# cube_bottom_4.net
KiCad netlist of a schematic drawn in EAGLE
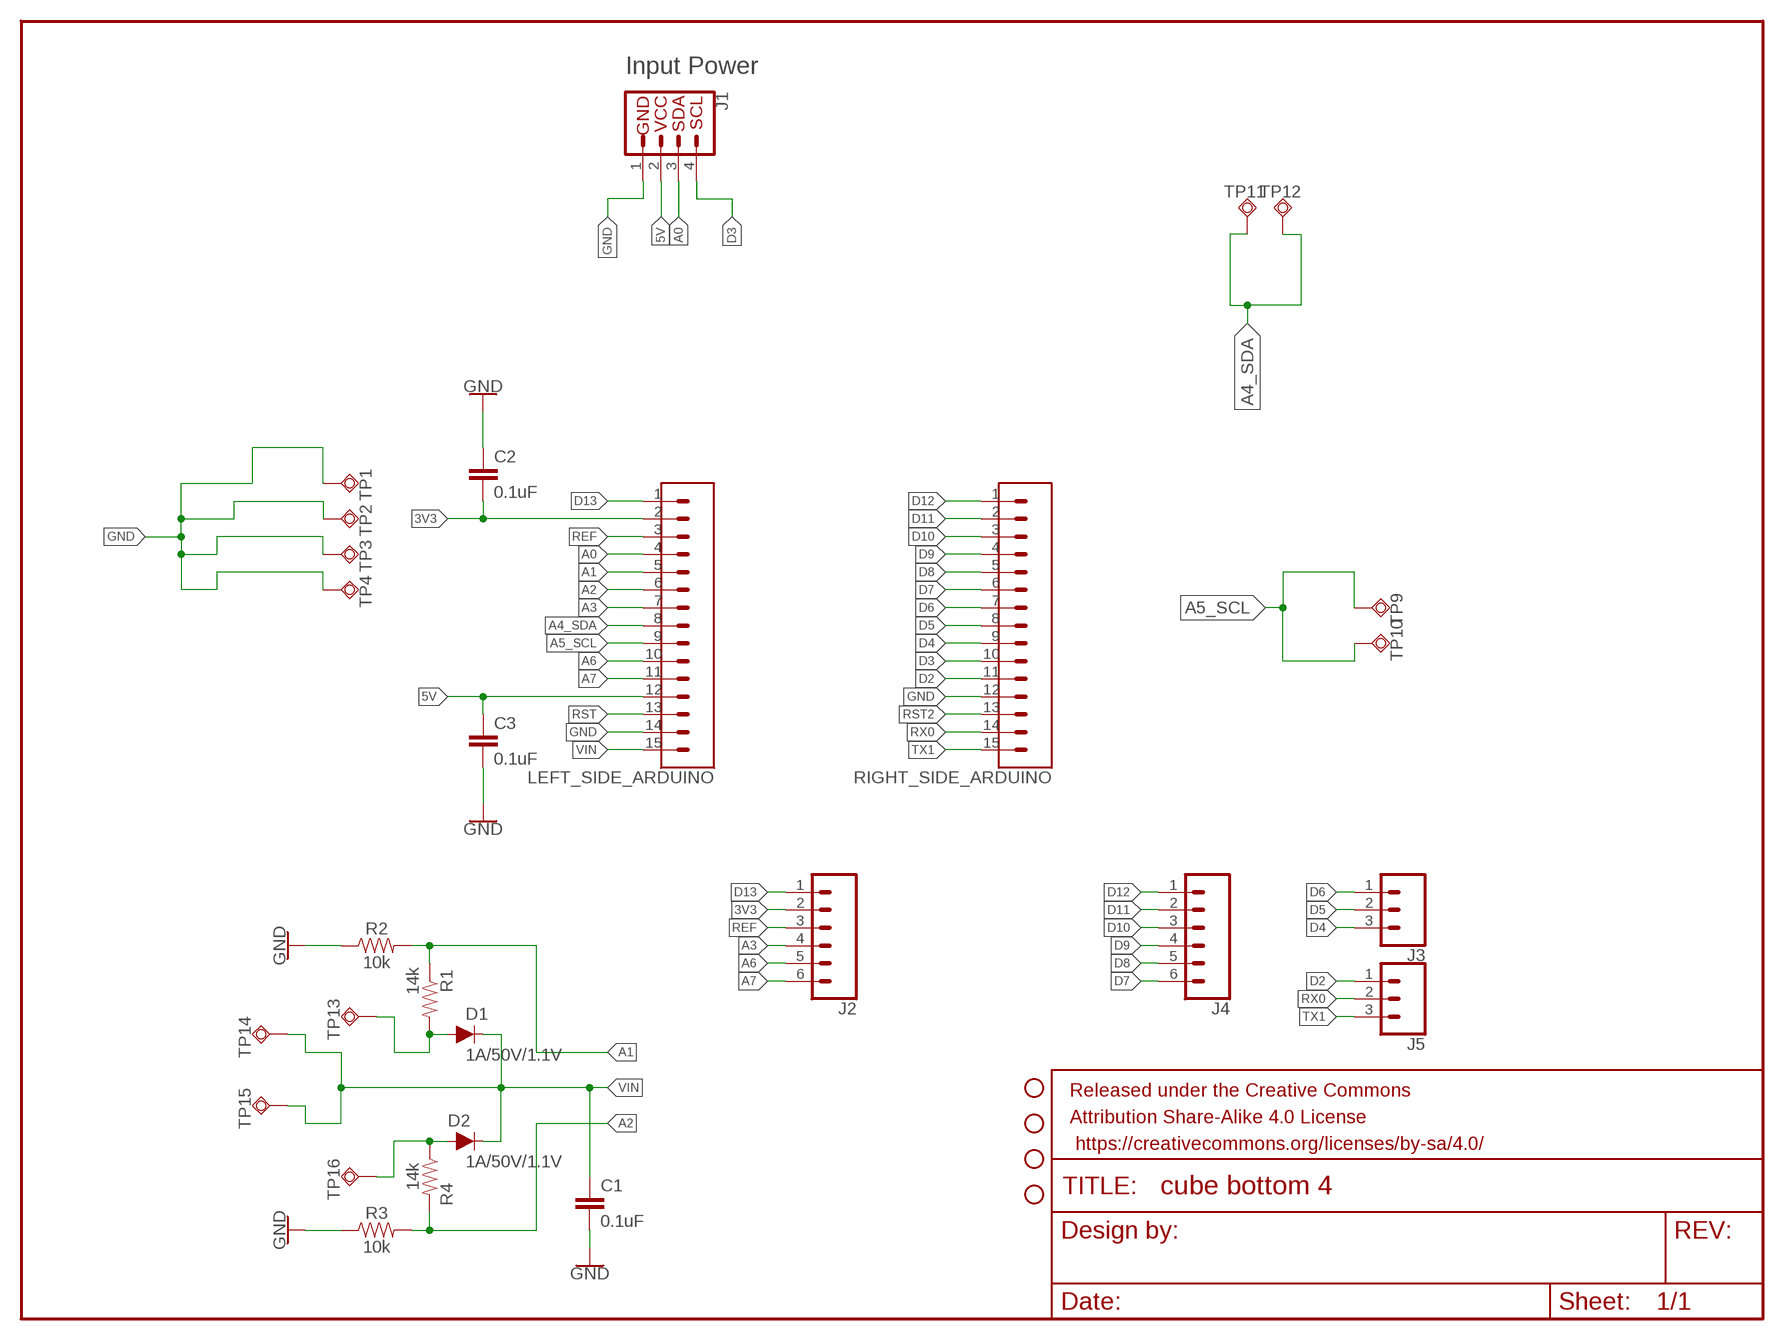
[diagram p0: schematic, sheet 1]

(export (version "E")
  (design (tool "Eeschema 10.0.6"))
  (components
    (comp (ref "C1")
      (value "0.1uF")
      (footprint "eagle-import:0603")
      (libsource (lib "eagle-import") (part "0.1UF-0603-25V-5%"))
    )
    (comp (ref "C2")
      (value "0.1uF")
      (footprint "eagle-import:0603")
      (libsource (lib "eagle-import") (part "0.1UF-0603-25V-(+80/-20%)"))
    )
    (comp (ref "C3")
      (value "0.1uF")
      (footprint "eagle-import:0603")
      (libsource (lib "eagle-import") (part "0.1UF-0603-25V-(+80/-20%)"))
    )
    (comp (ref "D1")
      (value "1A/50V/1.1V")
      (footprint "eagle-import:DIODE-1N4001")
      (libsource (lib "eagle-import") (part "DIODE-PTH"))
    )
    (comp (ref "D2")
      (value "1A/50V/1.1V")
      (footprint "eagle-import:DIODE-1N4001")
      (libsource (lib "eagle-import") (part "DIODE-PTH"))
    )
    (comp (ref "FRAME1")
      (value "FRAME-LETTERNO_PACKAGE")
      (footprint "eagle-import:DUMMY")
      (fields (field (name "DESIGNER") "Nobody"))
      (libsource (lib "eagle-import") (part "FRAME-LETTERNO_PACKAGE"))
    )
    (comp (ref "H1")
      (value "STAND-OFF")
      (footprint "eagle-import:STAND-OFF")
      (libsource (lib "eagle-import") (part "STAND-OFF"))
    )
    (comp (ref "H2")
      (value "STAND-OFF")
      (footprint "eagle-import:STAND-OFF")
      (libsource (lib "eagle-import") (part "STAND-OFF"))
    )
    (comp (ref "H3")
      (value "STAND-OFF")
      (footprint "eagle-import:STAND-OFF")
      (libsource (lib "eagle-import") (part "STAND-OFF"))
    )
    (comp (ref "H4")
      (value "STAND-OFF")
      (footprint "eagle-import:STAND-OFF")
      (libsource (lib "eagle-import") (part "STAND-OFF"))
    )
    (comp (ref "J1")
      (value "QWIIC_CONNECTORJS-1MM")
      (footprint "eagle-import:1X04_1MM_RA")
      (libsource (lib "eagle-import") (part "QWIIC_CONNECTORJS-1MM"))
    )
    (comp (ref "J2")
      (value "CONN_06SILK_FEMALE_PTH")
      (footprint "eagle-import:1X06")
      (libsource (lib "eagle-import") (part "CONN_06SILK_FEMALE_PTH"))
    )
    (comp (ref "J3")
      (value "CONN_03")
      (footprint "eagle-import:1X03")
      (libsource (lib "eagle-import") (part "CONN_03"))
    )
    (comp (ref "J4")
      (value "CONN_06SILK_FEMALE_PTH")
      (footprint "eagle-import:1X06")
      (libsource (lib "eagle-import") (part "CONN_06SILK_FEMALE_PTH"))
    )
    (comp (ref "J5")
      (value "CONN_03")
      (footprint "eagle-import:1X03")
      (libsource (lib "eagle-import") (part "CONN_03"))
    )
    (comp (ref "LEFT_SIDE_ARDUINO")
      (value "CONN_06SMD_MALE")
      (footprint "eagle-import:1X15_SMD_MALE")
      (libsource (lib "eagle-import") (part "capstone footprints_CONN_06SMD_MALE"))
    )
    (comp (ref "R1")
      (value "14k")
      (footprint "eagle-import:0603")
      (libsource (lib "eagle-import") (part "10KOHM-0603-1/10W-1%"))
    )
    (comp (ref "R2")
      (value "10k")
      (footprint "eagle-import:0603")
      (libsource (lib "eagle-import") (part "10KOHM-0603-1/10W-1%"))
    )
    (comp (ref "R3")
      (value "10k")
      (footprint "eagle-import:0603")
      (libsource (lib "eagle-import") (part "10KOHM-0603-1/10W-1%"))
    )
    (comp (ref "R4")
      (value "14k")
      (footprint "eagle-import:0603")
      (libsource (lib "eagle-import") (part "10KOHM-0603-1/10W-1%"))
    )
    (comp (ref "RIGHT_SIDE_ARDUINO")
      (value "CONN_06SMD_MALE")
      (footprint "eagle-import:1X15_SMD_MALE")
      (libsource (lib "eagle-import") (part "capstone footprints_CONN_06SMD_MALE"))
    )
    (comp (ref "TP1")
      (value "TPSQTP20SQ")
      (footprint "eagle-import:TP20SQ")
      (libsource (lib "eagle-import") (part "TPSQTP20SQ"))
    )
    (comp (ref "TP2")
      (value "TPSQTP20SQ")
      (footprint "eagle-import:TP20SQ")
      (libsource (lib "eagle-import") (part "TPSQTP20SQ"))
    )
    (comp (ref "TP3")
      (value "TPSQTP20SQ")
      (footprint "eagle-import:TP20SQ")
      (libsource (lib "eagle-import") (part "TPSQTP20SQ"))
    )
    (comp (ref "TP4")
      (value "TPSQTP20SQ")
      (footprint "eagle-import:TP20SQ")
      (libsource (lib "eagle-import") (part "TPSQTP20SQ"))
    )
    (comp (ref "TP9")
      (value "TPSQTP20SQ")
      (footprint "eagle-import:TP20SQ")
      (libsource (lib "eagle-import") (part "TPSQTP20SQ"))
    )
    (comp (ref "TP10")
      (value "TPSQTP20SQ")
      (footprint "eagle-import:TP20SQ")
      (libsource (lib "eagle-import") (part "TPSQTP20SQ"))
    )
    (comp (ref "TP11")
      (value "TPSQTP20SQ")
      (footprint "eagle-import:TP20SQ")
      (libsource (lib "eagle-import") (part "TPSQTP20SQ"))
    )
    (comp (ref "TP12")
      (value "TPSQTP20SQ")
      (footprint "eagle-import:TP20SQ")
      (libsource (lib "eagle-import") (part "TPSQTP20SQ"))
    )
    (comp (ref "TP13")
      (value "TPSQTP20SQ")
      (footprint "eagle-import:TP20SQ")
      (libsource (lib "eagle-import") (part "TPSQTP20SQ"))
    )
    (comp (ref "TP14")
      (value "TPSQTP20SQ")
      (footprint "eagle-import:TP20SQ")
      (libsource (lib "eagle-import") (part "TPSQTP20SQ"))
    )
    (comp (ref "TP15")
      (value "TPSQTP20SQ")
      (footprint "eagle-import:TP20SQ")
      (libsource (lib "eagle-import") (part "TPSQTP20SQ"))
    )
    (comp (ref "TP16")
      (value "TPSQTP20SQ")
      (footprint "eagle-import:TP20SQ")
      (libsource (lib "eagle-import") (part "TPSQTP20SQ"))
    )
  )
  (nets
    (net (code "1") (name "3V3") (class "Default")
      (node (ref "C2") (pin "2") (pinfunction "2_2") (pintype "passive"))
      (node (ref "J2") (pin "2") (pinfunction "2_2") (pintype "passive"))
      (node (ref "LEFT_SIDE_ARDUINO") (pin "2") (pinfunction "2_2") (pintype "passive"))
    )
    (net (code "2") (name "5V") (class "Default")
      (node (ref "C3") (pin "1") (pinfunction "1_1") (pintype "passive"))
      (node (ref "J1") (pin "2") (pinfunction "VCC_2") (pintype "power_in"))
      (node (ref "LEFT_SIDE_ARDUINO") (pin "12") (pinfunction "12_12") (pintype "passive"))
    )
    (net (code "3") (name "A0") (class "Default")
      (node (ref "J1") (pin "3") (pinfunction "SDA_3") (pintype "passive"))
      (node (ref "LEFT_SIDE_ARDUINO") (pin "4") (pinfunction "4_4") (pintype "passive"))
    )
    (net (code "4") (name "A1") (class "Default")
      (node (ref "LEFT_SIDE_ARDUINO") (pin "5") (pinfunction "5_5") (pintype "passive"))
      (node (ref "R1") (pin "1") (pinfunction "1_1") (pintype "passive"))
      (node (ref "R2") (pin "2") (pinfunction "2_2") (pintype "passive"))
    )
    (net (code "5") (name "A2") (class "Default")
      (node (ref "LEFT_SIDE_ARDUINO") (pin "6") (pinfunction "6_6") (pintype "passive"))
      (node (ref "R3") (pin "2") (pinfunction "2_2") (pintype "passive"))
      (node (ref "R4") (pin "2") (pinfunction "2_2") (pintype "passive"))
    )
    (net (code "6") (name "A3") (class "Default")
      (node (ref "J2") (pin "4") (pinfunction "4_4") (pintype "passive"))
      (node (ref "LEFT_SIDE_ARDUINO") (pin "7") (pinfunction "7_7") (pintype "passive"))
    )
    (net (code "7") (name "A4_SDA") (class "Default")
      (node (ref "LEFT_SIDE_ARDUINO") (pin "8") (pinfunction "8_8") (pintype "passive"))
      (node (ref "TP11") (pin "TP") (pinfunction "TP_TP") (pintype "input"))
      (node (ref "TP12") (pin "TP") (pinfunction "TP_TP") (pintype "input"))
    )
    (net (code "8") (name "A5_SCL") (class "Default")
      (node (ref "LEFT_SIDE_ARDUINO") (pin "9") (pinfunction "9_9") (pintype "passive"))
      (node (ref "TP10") (pin "TP") (pinfunction "TP_TP") (pintype "input"))
      (node (ref "TP9") (pin "TP") (pinfunction "TP_TP") (pintype "input"))
    )
    (net (code "9") (name "A6") (class "Default")
      (node (ref "J2") (pin "5") (pinfunction "5_5") (pintype "passive"))
      (node (ref "LEFT_SIDE_ARDUINO") (pin "10") (pinfunction "10_10") (pintype "passive"))
    )
    (net (code "10") (name "A7") (class "Default")
      (node (ref "J2") (pin "6") (pinfunction "6_6") (pintype "passive"))
      (node (ref "LEFT_SIDE_ARDUINO") (pin "11") (pinfunction "11_11") (pintype "passive"))
    )
    (net (code "11") (name "D2") (class "Default")
      (node (ref "J5") (pin "1") (pinfunction "1_1") (pintype "passive"))
      (node (ref "RIGHT_SIDE_ARDUINO") (pin "11") (pinfunction "11_11") (pintype "passive"))
    )
    (net (code "12") (name "D3") (class "Default")
      (node (ref "J1") (pin "4") (pinfunction "SCL_4") (pintype "passive"))
      (node (ref "RIGHT_SIDE_ARDUINO") (pin "10") (pinfunction "10_10") (pintype "passive"))
    )
    (net (code "13") (name "D4") (class "Default")
      (node (ref "J3") (pin "3") (pinfunction "3_3") (pintype "passive"))
      (node (ref "RIGHT_SIDE_ARDUINO") (pin "9") (pinfunction "9_9") (pintype "passive"))
    )
    (net (code "14") (name "D5") (class "Default")
      (node (ref "J3") (pin "2") (pinfunction "2_2") (pintype "passive"))
      (node (ref "RIGHT_SIDE_ARDUINO") (pin "8") (pinfunction "8_8") (pintype "passive"))
    )
    (net (code "15") (name "D6") (class "Default")
      (node (ref "J3") (pin "1") (pinfunction "1_1") (pintype "passive"))
      (node (ref "RIGHT_SIDE_ARDUINO") (pin "7") (pinfunction "7_7") (pintype "passive"))
    )
    (net (code "16") (name "D7") (class "Default")
      (node (ref "J4") (pin "6") (pinfunction "6_6") (pintype "passive"))
      (node (ref "RIGHT_SIDE_ARDUINO") (pin "6") (pinfunction "6_6") (pintype "passive"))
    )
    (net (code "17") (name "D8") (class "Default")
      (node (ref "J4") (pin "5") (pinfunction "5_5") (pintype "passive"))
      (node (ref "RIGHT_SIDE_ARDUINO") (pin "5") (pinfunction "5_5") (pintype "passive"))
    )
    (net (code "18") (name "D9") (class "Default")
      (node (ref "J4") (pin "4") (pinfunction "4_4") (pintype "passive"))
      (node (ref "RIGHT_SIDE_ARDUINO") (pin "4") (pinfunction "4_4") (pintype "passive"))
    )
    (net (code "19") (name "D10") (class "Default")
      (node (ref "J4") (pin "3") (pinfunction "3_3") (pintype "passive"))
      (node (ref "RIGHT_SIDE_ARDUINO") (pin "3") (pinfunction "3_3") (pintype "passive"))
    )
    (net (code "20") (name "D11") (class "Default")
      (node (ref "J4") (pin "2") (pinfunction "2_2") (pintype "passive"))
      (node (ref "RIGHT_SIDE_ARDUINO") (pin "2") (pinfunction "2_2") (pintype "passive"))
    )
    (net (code "21") (name "D12") (class "Default")
      (node (ref "J4") (pin "1") (pinfunction "1_1") (pintype "passive"))
      (node (ref "RIGHT_SIDE_ARDUINO") (pin "1") (pinfunction "1_1") (pintype "passive"))
    )
    (net (code "22") (name "D13") (class "Default")
      (node (ref "J2") (pin "1") (pinfunction "1_1") (pintype "passive"))
      (node (ref "LEFT_SIDE_ARDUINO") (pin "1") (pinfunction "1_1") (pintype "passive"))
    )
    (net (code "23") (name "GND") (class "Default")
      (node (ref "C1") (pin "2") (pinfunction "2_2") (pintype "passive"))
      (node (ref "C2") (pin "1") (pinfunction "1_1") (pintype "passive"))
      (node (ref "C3") (pin "2") (pinfunction "2_2") (pintype "passive"))
      (node (ref "J1") (pin "1") (pinfunction "GND_1") (pintype "power_in"))
      (node (ref "LEFT_SIDE_ARDUINO") (pin "14") (pinfunction "14_14") (pintype "passive"))
      (node (ref "R2") (pin "1") (pinfunction "1_1") (pintype "passive"))
      (node (ref "R3") (pin "1") (pinfunction "1_1") (pintype "passive"))
      (node (ref "RIGHT_SIDE_ARDUINO") (pin "12") (pinfunction "12_12") (pintype "passive"))
      (node (ref "TP1") (pin "TP") (pinfunction "TP_TP") (pintype "input"))
      (node (ref "TP2") (pin "TP") (pinfunction "TP_TP") (pintype "input"))
      (node (ref "TP3") (pin "TP") (pinfunction "TP_TP") (pintype "input"))
      (node (ref "TP4") (pin "TP") (pinfunction "TP_TP") (pintype "input"))
    )
    (net (code "24") (name "Net-(D1-PadA)") (class "Default")
      (node (ref "D1") (pin "A") (pinfunction "A_A") (pintype "passive"))
      (node (ref "R1") (pin "2") (pinfunction "2_2") (pintype "passive"))
      (node (ref "TP13") (pin "TP") (pinfunction "TP_TP") (pintype "input"))
    )
    (net (code "25") (name "Net-(D2-PadA)") (class "Default")
      (node (ref "D2") (pin "A") (pinfunction "A_A") (pintype "passive"))
      (node (ref "R4") (pin "1") (pinfunction "1_1") (pintype "passive"))
      (node (ref "TP16") (pin "TP") (pinfunction "TP_TP") (pintype "input"))
    )
    (net (code "26") (name "REF") (class "Default")
      (node (ref "J2") (pin "3") (pinfunction "3_3") (pintype "passive"))
      (node (ref "LEFT_SIDE_ARDUINO") (pin "3") (pinfunction "3_3") (pintype "passive"))
    )
    (net (code "27") (name "RST") (class "Default")
      (node (ref "LEFT_SIDE_ARDUINO") (pin "13") (pinfunction "13_13") (pintype "passive"))
    )
    (net (code "28") (name "RST2") (class "Default")
      (node (ref "RIGHT_SIDE_ARDUINO") (pin "13") (pinfunction "13_13") (pintype "passive"))
    )
    (net (code "29") (name "RX0") (class "Default")
      (node (ref "J5") (pin "2") (pinfunction "2_2") (pintype "passive"))
      (node (ref "RIGHT_SIDE_ARDUINO") (pin "14") (pinfunction "14_14") (pintype "passive"))
    )
    (net (code "30") (name "TX1") (class "Default")
      (node (ref "J5") (pin "3") (pinfunction "3_3") (pintype "passive"))
      (node (ref "RIGHT_SIDE_ARDUINO") (pin "15") (pinfunction "15_15") (pintype "passive"))
    )
    (net (code "31") (name "VIN") (class "Default")
      (node (ref "C1") (pin "1") (pinfunction "1_1") (pintype "passive"))
      (node (ref "D1") (pin "C") (pinfunction "C_C") (pintype "passive"))
      (node (ref "D2") (pin "C") (pinfunction "C_C") (pintype "passive"))
      (node (ref "LEFT_SIDE_ARDUINO") (pin "15") (pinfunction "15_15") (pintype "passive"))
      (node (ref "TP14") (pin "TP") (pinfunction "TP_TP") (pintype "input"))
      (node (ref "TP15") (pin "TP") (pinfunction "TP_TP") (pintype "input"))
    )
  )
)
